# Proyecto_Reinaldo.net
KiCad netlist of a schematic drawn in EAGLE
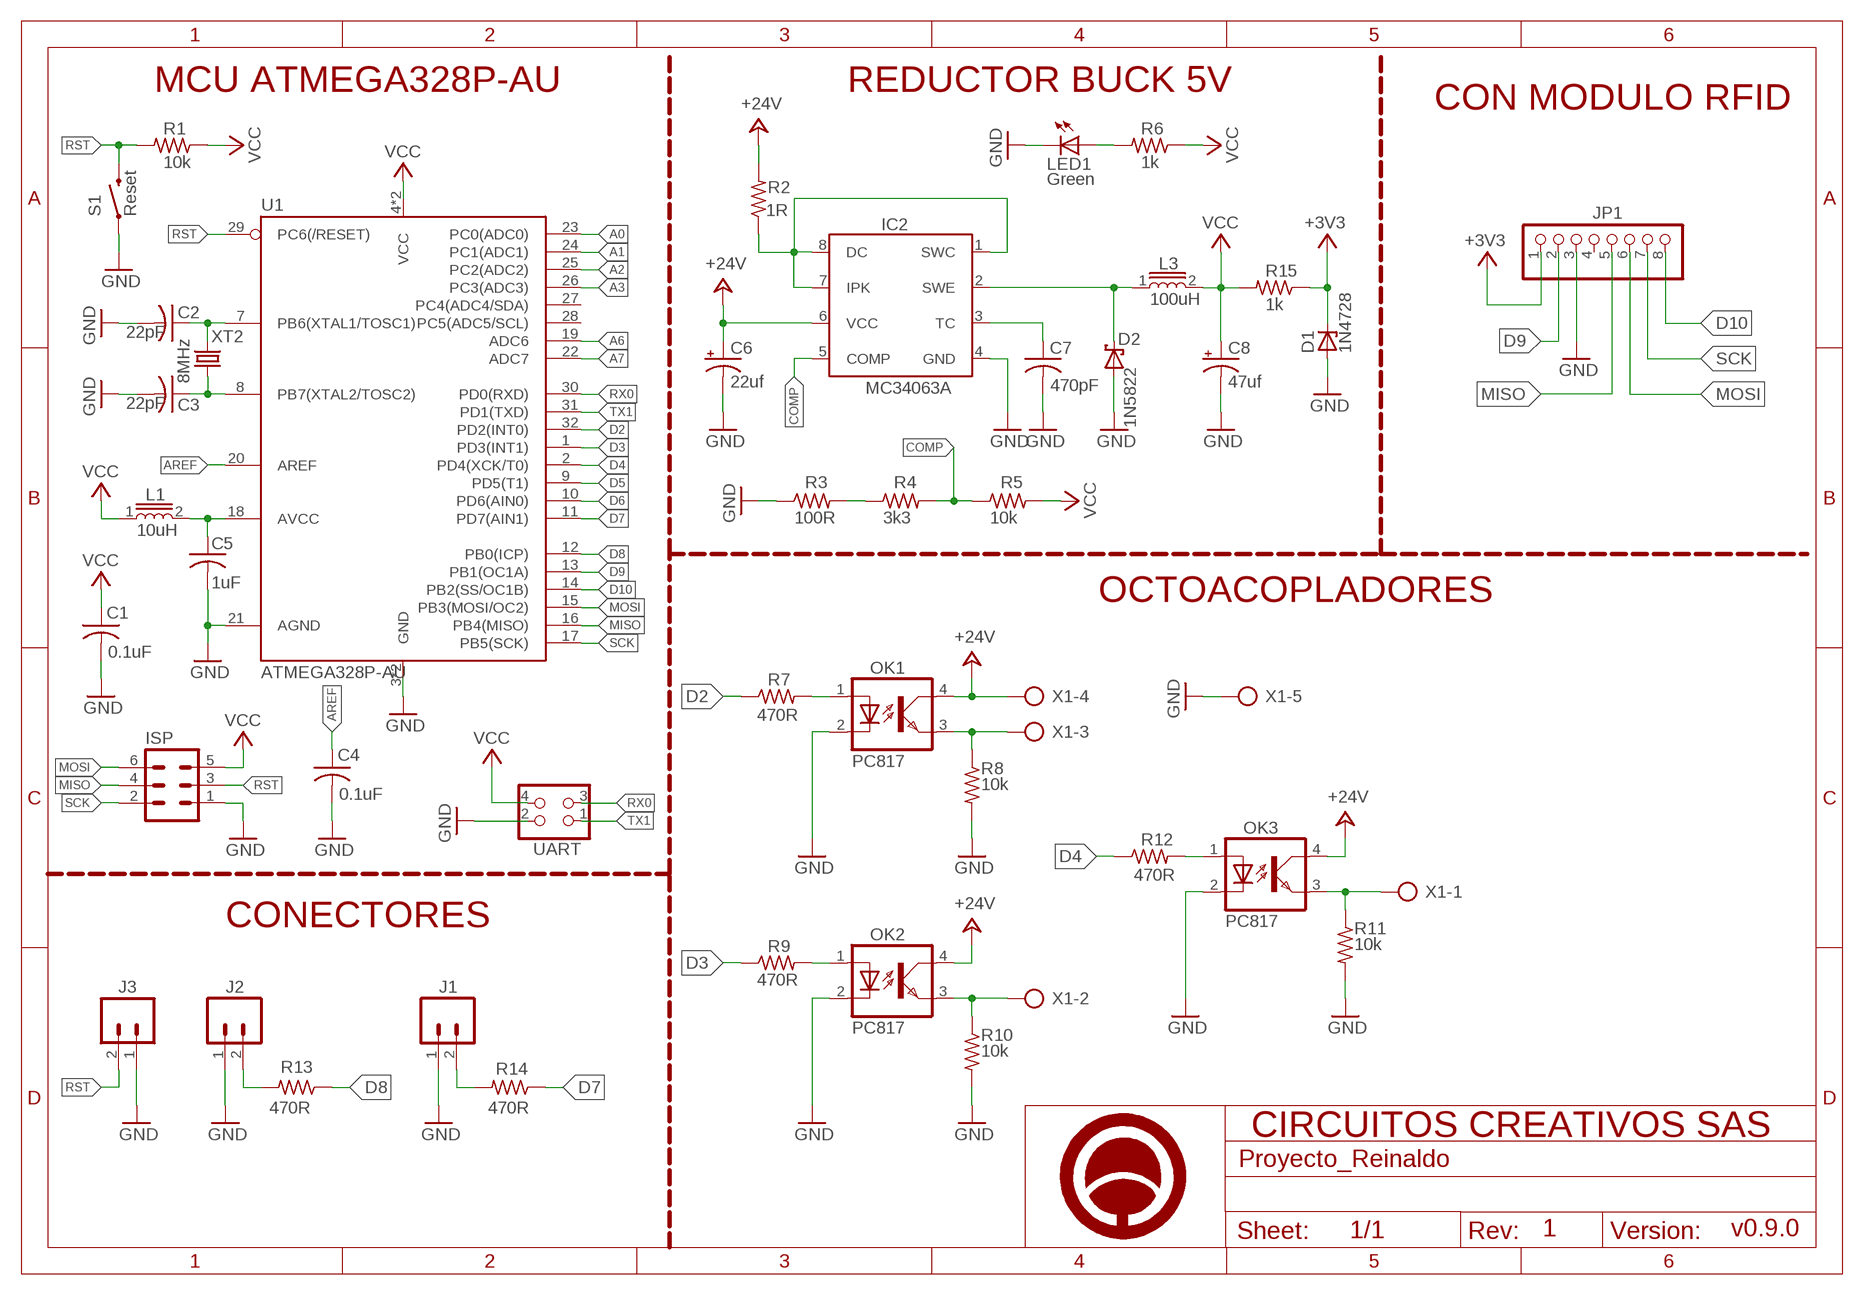
[diagram p0: schematic, sheet 1]

(export (version "E")
  (design (tool "Eeschema 10.0.6"))
  (components
    (comp (ref "C1")
      (value "0.1uF")
      (footprint "eagle-import:C0805")
      (libsource (lib "eagle-import") (part "C-USC0805"))
    )
    (comp (ref "C2")
      (value "22pF")
      (footprint "eagle-import:C0805")
      (libsource (lib "eagle-import") (part "C-USC0805"))
    )
    (comp (ref "C3")
      (value "22pF")
      (footprint "eagle-import:C0805")
      (libsource (lib "eagle-import") (part "C-USC0805"))
    )
    (comp (ref "C4")
      (value "0.1uF")
      (footprint "eagle-import:C0805")
      (libsource (lib "eagle-import") (part "C-USC0805"))
    )
    (comp (ref "C5")
      (value "1uF")
      (footprint "eagle-import:C0805")
      (libsource (lib "eagle-import") (part "C-USC0805"))
    )
    (comp (ref "C6")
      (value "22uf")
      (footprint "eagle-import:E2,5-6E")
      (libsource (lib "eagle-import") (part "CPOL-USE2,5-6E"))
    )
    (comp (ref "C7")
      (value "470pF")
      (footprint "eagle-import:C0805")
      (libsource (lib "eagle-import") (part "C-USC0805"))
    )
    (comp (ref "C8")
      (value "47uf")
      (footprint "eagle-import:E2,5-6E")
      (libsource (lib "eagle-import") (part "CPOL-USE2,5-6E"))
    )
    (comp (ref "D1")
      (value "1N4728")
      (footprint "eagle-import:DO41Z10")
      (libsource (lib "eagle-import") (part "1N4728"))
    )
    (comp (ref "D2")
      (value "1N5822")
      (footprint "eagle-import:DO-214AC")
      (libsource (lib "eagle-import") (part "1N5822"))
    )
    (comp (ref "IC2")
      (value "MC34063A")
      (footprint "eagle-import:SOIC-8")
      (libsource (lib "eagle-import") (part "MC34063A"))
    )
    (comp (ref "ISP")
      (value "MA03-2")
      (footprint "eagle-import:MA03-2")
      (libsource (lib "eagle-import") (part "MA03-2"))
    )
    (comp (ref "J1")
      (value "M02LOCK")
      (footprint "eagle-import:1X02_LOCK")
      (libsource (lib "eagle-import") (part "M02LOCK"))
    )
    (comp (ref "J2")
      (value "M02LOCK")
      (footprint "eagle-import:1X02_LOCK")
      (libsource (lib "eagle-import") (part "M02LOCK"))
    )
    (comp (ref "J3")
      (value "M02LOCK")
      (footprint "eagle-import:1X02_LOCK")
      (libsource (lib "eagle-import") (part "M02LOCK"))
    )
    (comp (ref "JP1")
      (value "PINHD-1X8BIG")
      (footprint "eagle-import:1X08-BIG")
      (libsource (lib "eagle-import") (part "PINHD-1X8BIG"))
    )
    (comp (ref "L1")
      (value "10uH")
      (footprint "eagle-import:L0805")
      (libsource (lib "eagle-import") (part "FERRITA-CHOKE"))
    )
    (comp (ref "L3")
      (value "100uH")
      (footprint "eagle-import:CD54")
      (libsource (lib "eagle-import") (part "CD54"))
    )
    (comp (ref "LED1")
      (value "Green")
      (footprint "eagle-import:CHIPLED_0805")
      (libsource (lib "eagle-import") (part "LEDCHIPLED_0805"))
    )
    (comp (ref "OK1")
      (value "PC817")
      (footprint "eagle-import:DIL04")
      (fields (field (name "MPN") "PC817X4J000F"))
      (libsource (lib "eagle-import") (part "PC817"))
    )
    (comp (ref "OK2")
      (value "PC817")
      (footprint "eagle-import:DIL04")
      (fields (field (name "MPN") "PC817X4J000F"))
      (libsource (lib "eagle-import") (part "PC817"))
    )
    (comp (ref "OK3")
      (value "PC817")
      (footprint "eagle-import:DIL04")
      (fields (field (name "MPN") "PC817X4J000F"))
      (libsource (lib "eagle-import") (part "PC817"))
    )
    (comp (ref "R1")
      (value "10k")
      (footprint "eagle-import:R1206")
      (libsource (lib "eagle-import") (part "RESISTORR1206"))
    )
    (comp (ref "R2")
      (value "1R")
      (footprint "eagle-import:R1206")
      (libsource (lib "eagle-import") (part "RESISTORR1206"))
    )
    (comp (ref "R3")
      (value "100R")
      (footprint "eagle-import:R1206")
      (libsource (lib "eagle-import") (part "RESISTORR1206"))
    )
    (comp (ref "R4")
      (value "3k3")
      (footprint "eagle-import:R1206")
      (libsource (lib "eagle-import") (part "RESISTORR1206"))
    )
    (comp (ref "R5")
      (value "10k")
      (footprint "eagle-import:R1206")
      (libsource (lib "eagle-import") (part "RESISTORR1206"))
    )
    (comp (ref "R6")
      (value "1k")
      (footprint "eagle-import:R1206")
      (libsource (lib "eagle-import") (part "RESISTORR1206"))
    )
    (comp (ref "R7")
      (value "470R")
      (footprint "eagle-import:R1206")
      (libsource (lib "eagle-import") (part "RESISTORR1206"))
    )
    (comp (ref "R8")
      (value "10k")
      (footprint "eagle-import:R1206")
      (libsource (lib "eagle-import") (part "RESISTORR1206"))
    )
    (comp (ref "R9")
      (value "470R")
      (footprint "eagle-import:R1206")
      (libsource (lib "eagle-import") (part "RESISTORR1206"))
    )
    (comp (ref "R10")
      (value "10k")
      (footprint "eagle-import:R1206")
      (libsource (lib "eagle-import") (part "RESISTORR1206"))
    )
    (comp (ref "R11")
      (value "10k")
      (footprint "eagle-import:R1206")
      (libsource (lib "eagle-import") (part "RESISTORR1206"))
    )
    (comp (ref "R12")
      (value "470R")
      (footprint "eagle-import:R1206")
      (libsource (lib "eagle-import") (part "RESISTORR1206"))
    )
    (comp (ref "R13")
      (value "470R")
      (footprint "eagle-import:R1206")
      (libsource (lib "eagle-import") (part "RESISTORR1206"))
    )
    (comp (ref "R14")
      (value "470R")
      (footprint "eagle-import:R1206")
      (libsource (lib "eagle-import") (part "RESISTORR1206"))
    )
    (comp (ref "R15")
      (value "1k")
      (footprint "eagle-import:R1206")
      (libsource (lib "eagle-import") (part "R-US_R1206"))
    )
    (comp (ref "S1")
      (value "Reset")
      (footprint "eagle-import:TACTILE-SWITCH-1101NE")
      (libsource (lib "eagle-import") (part "SWITCH-MOMENTARY-2-SMD-1101NE"))
    )
    (comp (ref "U$1")
      (value "A4_HORIZONTAL")
      (footprint "eagle-import:LOGO")
      (libsource (lib "eagle-import") (part "A4_HORIZONTAL"))
    )
    (comp (ref "U1")
      (value "ATMEGA328P-AU")
      (footprint "eagle-import:TQFP32")
      (libsource (lib "eagle-import") (part "ATMEGA328P-AU"))
    )
    (comp (ref "UART")
      (value "IPS_CIRCUITOS")
      (footprint "eagle-import:ISP_CIRCUITOS")
      (libsource (lib "eagle-import") (part "IPS_CIRCUITOS"))
    )
    (comp (ref "X1")
      (value "AK500/5")
      (footprint "eagle-import:AK500_5")
      (libsource (lib "eagle-import") (part "AK500/5"))
    )
    (comp (ref "XT2")
      (value "8MHz")
      (footprint "eagle-import:SM49")
      (libsource (lib "eagle-import") (part "CRYSTALSM49"))
    )
  )
  (nets
    (net (code "1") (name "+3V3") (class "Default")
      (node (ref "D1") (pin "C") (pinfunction "C_C") (pintype "passive"))
      (node (ref "JP1") (pin "1") (pinfunction "1_1") (pintype "passive"))
      (node (ref "R15") (pin "1") (pinfunction "1_1") (pintype "passive"))
    )
    (net (code "2") (name "+24V") (class "Default")
      (node (ref "C6") (pin "+") (pinfunction "+_+") (pintype "passive"))
      (node (ref "IC2") (pin "6") (pinfunction "VCC_6") (pintype "power_in"))
      (node (ref "OK1") (pin "4") (pinfunction "COL_4") (pintype "passive"))
      (node (ref "OK2") (pin "4") (pinfunction "COL_4") (pintype "passive"))
      (node (ref "OK3") (pin "4") (pinfunction "COL_4") (pintype "passive"))
      (node (ref "R2") (pin "2") (pinfunction "2_2") (pintype "passive"))
      (node (ref "X1") (pin "4") (pinfunction "KL_4") (pintype "passive"))
    )
    (net (code "3") (name "A0") (class "Default")
      (node (ref "U1") (pin "23") (pinfunction "PC0(ADC0)_23") (pintype "bidirectional"))
    )
    (net (code "4") (name "A1") (class "Default")
      (node (ref "U1") (pin "24") (pinfunction "PC1(ADC1)_24") (pintype "bidirectional"))
    )
    (net (code "5") (name "A2") (class "Default")
      (node (ref "U1") (pin "25") (pinfunction "PC2(ADC2)_25") (pintype "bidirectional"))
    )
    (net (code "6") (name "A3") (class "Default")
      (node (ref "U1") (pin "26") (pinfunction "PC3(ADC3)_26") (pintype "bidirectional"))
    )
    (net (code "7") (name "A6") (class "Default")
      (node (ref "U1") (pin "19") (pinfunction "ADC6_19") (pintype "bidirectional"))
    )
    (net (code "8") (name "A7") (class "Default")
      (node (ref "U1") (pin "22") (pinfunction "ADC7_22") (pintype "bidirectional"))
    )
    (net (code "9") (name "AREF") (class "Default")
      (node (ref "C4") (pin "1") (pinfunction "1_1") (pintype "passive"))
      (node (ref "U1") (pin "20") (pinfunction "AREF_20") (pintype "bidirectional"))
    )
    (net (code "10") (name "COMP") (class "Default")
      (node (ref "IC2") (pin "5") (pinfunction "COMP_5") (pintype "bidirectional"))
      (node (ref "R4") (pin "2") (pinfunction "2_2") (pintype "passive"))
      (node (ref "R5") (pin "1") (pinfunction "1_1") (pintype "passive"))
    )
    (net (code "11") (name "D2") (class "Default")
      (node (ref "R7") (pin "1") (pinfunction "1_1") (pintype "passive"))
      (node (ref "U1") (pin "32") (pinfunction "PD2(INT0)_32") (pintype "bidirectional"))
    )
    (net (code "12") (name "D3") (class "Default")
      (node (ref "R9") (pin "1") (pinfunction "1_1") (pintype "passive"))
      (node (ref "U1") (pin "1") (pinfunction "PD3(INT1)_1") (pintype "bidirectional"))
    )
    (net (code "13") (name "D4") (class "Default")
      (node (ref "R12") (pin "1") (pinfunction "1_1") (pintype "passive"))
      (node (ref "U1") (pin "2") (pinfunction "PD4(XCK/T0)_2") (pintype "bidirectional"))
    )
    (net (code "14") (name "D5") (class "Default")
      (node (ref "U1") (pin "9") (pinfunction "PD5(T1)_9") (pintype "bidirectional"))
    )
    (net (code "15") (name "D6") (class "Default")
      (node (ref "U1") (pin "10") (pinfunction "PD6(AIN0)_10") (pintype "bidirectional"))
    )
    (net (code "16") (name "D7") (class "Default")
      (node (ref "R14") (pin "1") (pinfunction "1_1") (pintype "passive"))
      (node (ref "U1") (pin "11") (pinfunction "PD7(AIN1)_11") (pintype "bidirectional"))
    )
    (net (code "17") (name "D8") (class "Default")
      (node (ref "R13") (pin "1") (pinfunction "1_1") (pintype "passive"))
      (node (ref "U1") (pin "12") (pinfunction "PB0(ICP)_12") (pintype "bidirectional"))
    )
    (net (code "18") (name "D9") (class "Default")
      (node (ref "JP1") (pin "2") (pinfunction "2_2") (pintype "passive"))
      (node (ref "U1") (pin "13") (pinfunction "PB1(OC1A)_13") (pintype "bidirectional"))
    )
    (net (code "19") (name "D10") (class "Default")
      (node (ref "JP1") (pin "8") (pinfunction "8_8") (pintype "passive"))
      (node (ref "U1") (pin "14") (pinfunction "PB2(SS/OC1B)_14") (pintype "bidirectional"))
    )
    (net (code "20") (name "GND") (class "Default")
      (node (ref "C1") (pin "2") (pinfunction "2_2") (pintype "passive"))
      (node (ref "C2") (pin "2") (pinfunction "2_2") (pintype "passive"))
      (node (ref "C3") (pin "2") (pinfunction "2_2") (pintype "passive"))
      (node (ref "C4") (pin "2") (pinfunction "2_2") (pintype "passive"))
      (node (ref "C5") (pin "2") (pinfunction "2_2") (pintype "passive"))
      (node (ref "C6") (pin "-") (pinfunction "-_-") (pintype "passive"))
      (node (ref "C7") (pin "2") (pinfunction "2_2") (pintype "passive"))
      (node (ref "C8") (pin "-") (pinfunction "-_-") (pintype "passive"))
      (node (ref "D1") (pin "A") (pinfunction "A_A") (pintype "passive"))
      (node (ref "D2") (pin "A") (pinfunction "A_A") (pintype "passive"))
      (node (ref "IC2") (pin "4") (pinfunction "GND_4") (pintype "power_in"))
      (node (ref "ISP") (pin "1") (pinfunction "1_1") (pintype "passive"))
      (node (ref "J1") (pin "1") (pinfunction "1_1") (pintype "passive"))
      (node (ref "J2") (pin "1") (pinfunction "1_1") (pintype "passive"))
      (node (ref "J3") (pin "1") (pinfunction "1_1") (pintype "passive"))
      (node (ref "JP1") (pin "3") (pinfunction "3_3") (pintype "passive"))
      (node (ref "LED1") (pin "C") (pinfunction "C_C") (pintype "passive"))
      (node (ref "OK1") (pin "2") (pinfunction "C_2") (pintype "passive"))
      (node (ref "OK2") (pin "2") (pinfunction "C_2") (pintype "passive"))
      (node (ref "OK3") (pin "2") (pinfunction "C_2") (pintype "passive"))
      (node (ref "R10") (pin "2") (pinfunction "2_2") (pintype "passive"))
      (node (ref "R11") (pin "2") (pinfunction "2_2") (pintype "passive"))
      (node (ref "R3") (pin "1") (pinfunction "1_1") (pintype "passive"))
      (node (ref "R8") (pin "2") (pinfunction "2_2") (pintype "passive"))
      (node (ref "S1") (pin "P$1") (pinfunction "1_P$1") (pintype "passive"))
      (node (ref "U1") (pin "21") (pinfunction "AGND_21") (pintype "bidirectional"))
      (node (ref "U1") (pin "3") (pinfunction "GND_3") (pintype "power_in"))
      (node (ref "U1") (pin "5") (pinfunction "GND_5") (pintype "power_in"))
      (node (ref "UART") (pin "2") (pinfunction "2_2") (pintype "passive"))
      (node (ref "X1") (pin "5") (pinfunction "KL_5") (pintype "passive"))
    )
    (net (code "21") (name "MISO") (class "Default")
      (node (ref "ISP") (pin "4") (pinfunction "4_4") (pintype "passive"))
      (node (ref "JP1") (pin "5") (pinfunction "5_5") (pintype "passive"))
      (node (ref "U1") (pin "16") (pinfunction "PB4(MISO)_16") (pintype "bidirectional"))
    )
    (net (code "22") (name "MOSI") (class "Default")
      (node (ref "ISP") (pin "6") (pinfunction "6_6") (pintype "passive"))
      (node (ref "JP1") (pin "6") (pinfunction "6_6") (pintype "passive"))
      (node (ref "U1") (pin "15") (pinfunction "PB3(MOSI/OC2)_15") (pintype "bidirectional"))
    )
    (net (code "23") (name "Net-(IC2-DC)") (class "Default")
      (node (ref "IC2") (pin "1") (pinfunction "SWC_1") (pintype "bidirectional"))
      (node (ref "IC2") (pin "7") (pinfunction "IPK_7") (pintype "bidirectional"))
      (node (ref "IC2") (pin "8") (pinfunction "DC_8") (pintype "bidirectional"))
      (node (ref "R2") (pin "1") (pinfunction "1_1") (pintype "passive"))
    )
    (net (code "24") (name "Net-(IC2-SWE)") (class "Default")
      (node (ref "D2") (pin "K") (pinfunction "K_K") (pintype "passive"))
      (node (ref "IC2") (pin "2") (pinfunction "SWE_2") (pintype "bidirectional"))
      (node (ref "L3") (pin "1") (pinfunction "1_1") (pintype "passive"))
    )
    (net (code "25") (name "Net-(IC2-TC)") (class "Default")
      (node (ref "C7") (pin "1") (pinfunction "1_1") (pintype "passive"))
      (node (ref "IC2") (pin "3") (pinfunction "TC_3") (pintype "bidirectional"))
    )
    (net (code "26") (name "Net-(J1-Pad2)") (class "Default")
      (node (ref "J1") (pin "2") (pinfunction "2_2") (pintype "passive"))
      (node (ref "R14") (pin "2") (pinfunction "2_2") (pintype "passive"))
    )
    (net (code "27") (name "Net-(J2-Pad2)") (class "Default")
      (node (ref "J2") (pin "2") (pinfunction "2_2") (pintype "passive"))
      (node (ref "R13") (pin "2") (pinfunction "2_2") (pintype "passive"))
    )
    (net (code "28") (name "Net-(LED1-PadA)") (class "Default")
      (node (ref "LED1") (pin "A") (pinfunction "A_A") (pintype "passive"))
      (node (ref "R6") (pin "2") (pinfunction "2_2") (pintype "passive"))
    )
    (net (code "29") (name "Net-(OK1-A)") (class "Default")
      (node (ref "OK1") (pin "1") (pinfunction "A_1") (pintype "passive"))
      (node (ref "R7") (pin "2") (pinfunction "2_2") (pintype "passive"))
    )
    (net (code "30") (name "Net-(OK1-EMIT)") (class "Default")
      (node (ref "OK1") (pin "3") (pinfunction "EMIT_3") (pintype "passive"))
      (node (ref "R8") (pin "1") (pinfunction "1_1") (pintype "passive"))
      (node (ref "X1") (pin "3") (pinfunction "KL_3") (pintype "passive"))
    )
    (net (code "31") (name "Net-(OK2-A)") (class "Default")
      (node (ref "OK2") (pin "1") (pinfunction "A_1") (pintype "passive"))
      (node (ref "R9") (pin "2") (pinfunction "2_2") (pintype "passive"))
    )
    (net (code "32") (name "Net-(OK2-EMIT)") (class "Default")
      (node (ref "OK2") (pin "3") (pinfunction "EMIT_3") (pintype "passive"))
      (node (ref "R10") (pin "1") (pinfunction "1_1") (pintype "passive"))
      (node (ref "X1") (pin "2") (pinfunction "KL_2") (pintype "passive"))
    )
    (net (code "33") (name "Net-(OK3-A)") (class "Default")
      (node (ref "OK3") (pin "1") (pinfunction "A_1") (pintype "passive"))
      (node (ref "R12") (pin "2") (pinfunction "2_2") (pintype "passive"))
    )
    (net (code "34") (name "Net-(OK3-EMIT)") (class "Default")
      (node (ref "OK3") (pin "3") (pinfunction "EMIT_3") (pintype "passive"))
      (node (ref "R11") (pin "1") (pinfunction "1_1") (pintype "passive"))
      (node (ref "X1") (pin "1") (pinfunction "KL_1") (pintype "passive"))
    )
    (net (code "35") (name "Net-(R3-Pad2)") (class "Default")
      (node (ref "R3") (pin "2") (pinfunction "2_2") (pintype "passive"))
      (node (ref "R4") (pin "1") (pinfunction "1_1") (pintype "passive"))
    )
    (net (code "36") (name "Net-(U1-AVCC)") (class "Default")
      (node (ref "C5") (pin "1") (pinfunction "1_1") (pintype "passive"))
      (node (ref "L1") (pin "2") (pinfunction "2_2") (pintype "passive"))
      (node (ref "U1") (pin "18") (pinfunction "AVCC_18") (pintype "bidirectional"))
    )
    (net (code "37") (name "Net-(U1-PB6(XTAL1{slash}TOSC1))") (class "Default")
      (node (ref "C2") (pin "1") (pinfunction "1_1") (pintype "passive"))
      (node (ref "U1") (pin "7") (pinfunction "PB6(XTAL1/TOSC1)_7") (pintype "bidirectional"))
      (node (ref "XT2") (pin "2") (pinfunction "2_2") (pintype "passive"))
    )
    (net (code "38") (name "Net-(U1-PB7(XTAL2{slash}TOSC2))") (class "Default")
      (node (ref "C3") (pin "1") (pinfunction "1_1") (pintype "passive"))
      (node (ref "U1") (pin "8") (pinfunction "PB7(XTAL2/TOSC2)_8") (pintype "bidirectional"))
      (node (ref "XT2") (pin "1") (pinfunction "1_1") (pintype "passive"))
    )
    (net (code "39") (name "RST") (class "Default")
      (node (ref "ISP") (pin "3") (pinfunction "3_3") (pintype "passive"))
      (node (ref "J3") (pin "2") (pinfunction "2_2") (pintype "passive"))
      (node (ref "R1") (pin "2") (pinfunction "2_2") (pintype "passive"))
      (node (ref "S1") (pin "P$2") (pinfunction "2_P$2") (pintype "passive"))
      (node (ref "U1") (pin "29") (pinfunction "PC6(/RESET)_29") (pintype "bidirectional"))
    )
    (net (code "40") (name "RX0") (class "Default")
      (node (ref "U1") (pin "30") (pinfunction "PD0(RXD)_30") (pintype "bidirectional"))
      (node (ref "UART") (pin "3") (pinfunction "3_3") (pintype "passive"))
    )
    (net (code "41") (name "SCK") (class "Default")
      (node (ref "ISP") (pin "2") (pinfunction "2_2") (pintype "passive"))
      (node (ref "JP1") (pin "7") (pinfunction "7_7") (pintype "passive"))
      (node (ref "U1") (pin "17") (pinfunction "PB5(SCK)_17") (pintype "bidirectional"))
    )
    (net (code "42") (name "TX1") (class "Default")
      (node (ref "U1") (pin "31") (pinfunction "PD1(TXD)_31") (pintype "bidirectional"))
      (node (ref "UART") (pin "1") (pinfunction "1_1") (pintype "passive"))
    )
    (net (code "43") (name "VCC") (class "Default")
      (node (ref "C1") (pin "1") (pinfunction "1_1") (pintype "passive"))
      (node (ref "C8") (pin "+") (pinfunction "+_+") (pintype "passive"))
      (node (ref "ISP") (pin "5") (pinfunction "5_5") (pintype "passive"))
      (node (ref "L1") (pin "1") (pinfunction "1_1") (pintype "passive"))
      (node (ref "L3") (pin "2") (pinfunction "2_2") (pintype "passive"))
      (node (ref "R1") (pin "1") (pinfunction "1_1") (pintype "passive"))
      (node (ref "R15") (pin "2") (pinfunction "2_2") (pintype "passive"))
      (node (ref "R5") (pin "2") (pinfunction "2_2") (pintype "passive"))
      (node (ref "R6") (pin "1") (pinfunction "1_1") (pintype "passive"))
      (node (ref "U1") (pin "4") (pinfunction "VCC_4") (pintype "power_in"))
      (node (ref "U1") (pin "6") (pinfunction "VCC_6") (pintype "power_in"))
      (node (ref "UART") (pin "4") (pinfunction "4_4") (pintype "passive"))
    )
    (net (code "44") (name "unconnected-(JP1-Pad4)") (class "Default")
      (node (ref "JP1") (pin "4") (pinfunction "4_4") (pintype "passive"))
    )
    (net (code "45") (name "unconnected-(U1-PC4(ADC4{slash}SDA)-Pad27)") (class "Default")
      (node (ref "U1") (pin "27") (pinfunction "PC4(ADC4/SDA)_27") (pintype "bidirectional"))
    )
    (net (code "46") (name "unconnected-(U1-PC5(ADC5{slash}SCL)-Pad28)") (class "Default")
      (node (ref "U1") (pin "28") (pinfunction "PC5(ADC5/SCL)_28") (pintype "bidirectional"))
    )
  )
)
